# fonte.net
KiCad netlist of a schematic drawn in EAGLE
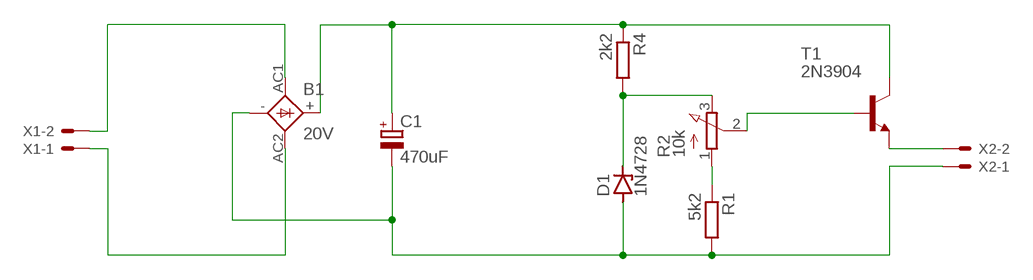
[diagram p0: schematic, sheet 1]

(export (version "E")
  (design (tool "Eeschema 10.0.6"))
  (components
    (comp (ref "B1")
      (value "20V")
      (footprint "eagle-import:1KAB")
      (libsource (lib "eagle-import") (part "1KAB"))
    )
    (comp (ref "C1")
      (value "470uF")
      (footprint "eagle-import:E2,5-6E")
      (libsource (lib "eagle-import") (part "CPOL-EUE2,5-6E"))
    )
    (comp (ref "D1")
      (value "1N4728")
      (footprint "eagle-import:DO41Z10")
      (libsource (lib "eagle-import") (part "1N4728"))
    )
    (comp (ref "R1")
      (value "5k2")
      (footprint "eagle-import:0207_10")
      (libsource (lib "eagle-import") (part "R-EU_0207/10"))
    )
    (comp (ref "R2")
      (value "10k")
      (footprint "eagle-import:3RP_1610N")
      (libsource (lib "eagle-import") (part "3RP/1610N"))
    )
    (comp (ref "R4")
      (value "2k2")
      (footprint "eagle-import:0207_10")
      (libsource (lib "eagle-import") (part "R-EU_0207/10"))
    )
    (comp (ref "T1")
      (value "2N3904")
      (footprint "eagle-import:TO92")
      (libsource (lib "eagle-import") (part "2N3904"))
    )
    (comp (ref "X1")
      (value "22-23-2021")
      (footprint "eagle-import:22-23-2021")
      (fields (field (name "MF") "MOLEX"))
      (libsource (lib "eagle-import") (part "22-23-2021"))
    )
    (comp (ref "X2")
      (value "22-23-2021")
      (footprint "eagle-import:22-23-2021")
      (fields (field (name "MF") "MOLEX"))
      (libsource (lib "eagle-import") (part "22-23-2021"))
    )
  )
  (nets
    (net (code "1") (name "Net-(R2-A)") (class "Default")
      (node (ref "R1") (pin "1") (pinfunction "1_1") (pintype "passive"))
      (node (ref "R2") (pin "1") (pinfunction "A_1") (pintype "passive"))
    )
    (net (code "2") (name "Net-(R2-E)") (class "Default")
      (node (ref "D1") (pin "C") (pinfunction "C_C") (pintype "passive"))
      (node (ref "R2") (pin "3") (pinfunction "E_3") (pintype "passive"))
      (node (ref "R4") (pin "2") (pinfunction "2_2") (pintype "passive"))
    )
    (net (code "3") (name "Net-(R2-S)") (class "Default")
      (node (ref "R2") (pin "2") (pinfunction "S_2") (pintype "passive"))
      (node (ref "T1") (pin "2") (pinfunction "B_2") (pintype "passive"))
    )
    (net (code "4") (name "Net-(T1-C)") (class "Default")
      (node (ref "B1") (pin "+") (pinfunction "+_+") (pintype "passive"))
      (node (ref "C1") (pin "+") (pinfunction "+_+") (pintype "passive"))
      (node (ref "R4") (pin "1") (pinfunction "1_1") (pintype "passive"))
      (node (ref "T1") (pin "1") (pinfunction "C_1") (pintype "passive"))
    )
    (net (code "5") (name "Net-(T1-E)") (class "Default")
      (node (ref "T1") (pin "3") (pinfunction "E_3") (pintype "passive"))
      (node (ref "X2") (pin "2") (pinfunction "S_2") (pintype "passive"))
    )
    (net (code "6") (name "Net-(X1A-S)") (class "Default")
      (node (ref "B1") (pin "AC2") (pinfunction "AC2_AC2") (pintype "passive"))
      (node (ref "X1") (pin "1") (pinfunction "S_1") (pintype "passive"))
    )
    (net (code "7") (name "Net-(X1B-S)") (class "Default")
      (node (ref "B1") (pin "AC1") (pinfunction "AC1_AC1") (pintype "passive"))
      (node (ref "X1") (pin "2") (pinfunction "S_2") (pintype "passive"))
    )
    (net (code "8") (name "Net-(X2A-S)") (class "Default")
      (node (ref "B1") (pin "-") (pinfunction "-_-") (pintype "passive"))
      (node (ref "C1") (pin "-") (pinfunction "-_-") (pintype "passive"))
      (node (ref "D1") (pin "A") (pinfunction "A_A") (pintype "passive"))
      (node (ref "R1") (pin "2") (pinfunction "2_2") (pintype "passive"))
      (node (ref "X2") (pin "1") (pinfunction "S_1") (pintype "passive"))
    )
  )
)
